# 02_boost5v.net
KiCad netlist of a schematic drawn in Altium Designer
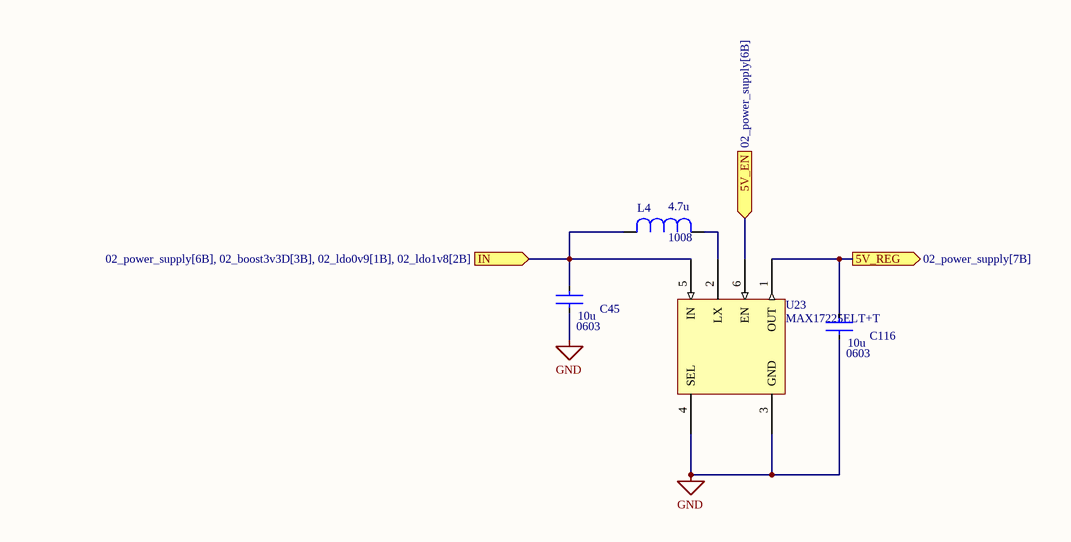
[diagram p0: 02_boost5v.SchDoc]

(export (version "E")
  (design (tool "Eeschema 10.0.6"))
  (components
    (comp (ref "C45")
      (value "C1608X5R1A106K080AC")
      (footprint "CAPTDK0603")
      (description "CAP CER 10UF 10V X5R 0603")
      (libsource (lib "tcspc00") (part "C1608X5R1A106K080AC"))
    )
    (comp (ref "C116")
      (value "C1608X5R1A106K080AC")
      (footprint "CAPTDK0603")
      (description "CAP CER 10UF 10V X5R 0603")
      (libsource (lib "tcspc00") (part "C1608X5R1A106K080AC"))
    )
    (comp (ref "L4")
      (value "1269AS-H-4R7M=P2")
      (footprint "INDMURT1008")
      (description "FIXED IND 4.7UH 1.3A 300MOHM SMD")
      (fields (field (name "DIGI-KEY_PART_NUMBER") "490-10577-1-ND") (field (name "MF") "Murata Electronics"))
      (libsource (lib "tcspc00") (part "1269AS-H-4R7M=P2"))
    )
    (comp (ref "U23")
      (value "MAX17225ELT+T")
      (footprint "MAX17222ELT+T")
      (description "IC REG 0.9V TO 5V 1A 6UDFN")
      (fields (field (name "COPYRIGHT") "Copyright (C) 2022 Ultra Librarian. All rights reserved."))
      (libsource (lib "tcspc00") (part "MAX17225ELT+T"))
    )
  )
  (nets
    (net (code "1") (name "/5V_EN") (class "Default")
      (node (ref "U23") (pin "6") (pinfunction "EN_6") (pintype "input"))
    )
    (net (code "2") (name "/5V_REG") (class "Default")
      (node (ref "C116") (pin "1") (pinfunction "1_1") (pintype "passive"))
      (node (ref "U23") (pin "1") (pinfunction "OUT_1") (pintype "output"))
    )
    (net (code "3") (name "/IN") (class "Default")
      (node (ref "C45") (pin "1") (pinfunction "1_1") (pintype "passive"))
      (node (ref "L4") (pin "2") (pinfunction "2_2") (pintype "passive"))
      (node (ref "U23") (pin "5") (pinfunction "IN_5") (pintype "input"))
    )
    (net (code "4") (name "GND") (class "Default")
      (node (ref "C116") (pin "2") (pinfunction "2_2") (pintype "passive"))
      (node (ref "C45") (pin "2") (pinfunction "2_2") (pintype "passive"))
      (node (ref "U23") (pin "3") (pinfunction "GND_3") (pintype "passive"))
      (node (ref "U23") (pin "4") (pinfunction "SEL_4") (pintype "passive"))
    )
    (net (code "5") (name "Net-(U23-LX)") (class "Default")
      (node (ref "L4") (pin "1") (pinfunction "1_1") (pintype "passive"))
      (node (ref "U23") (pin "2") (pinfunction "LX_2") (pintype "passive"))
    )
  )
)
